# PS2Kbd.net
KiCad netlist of a schematic drawn in EAGLE
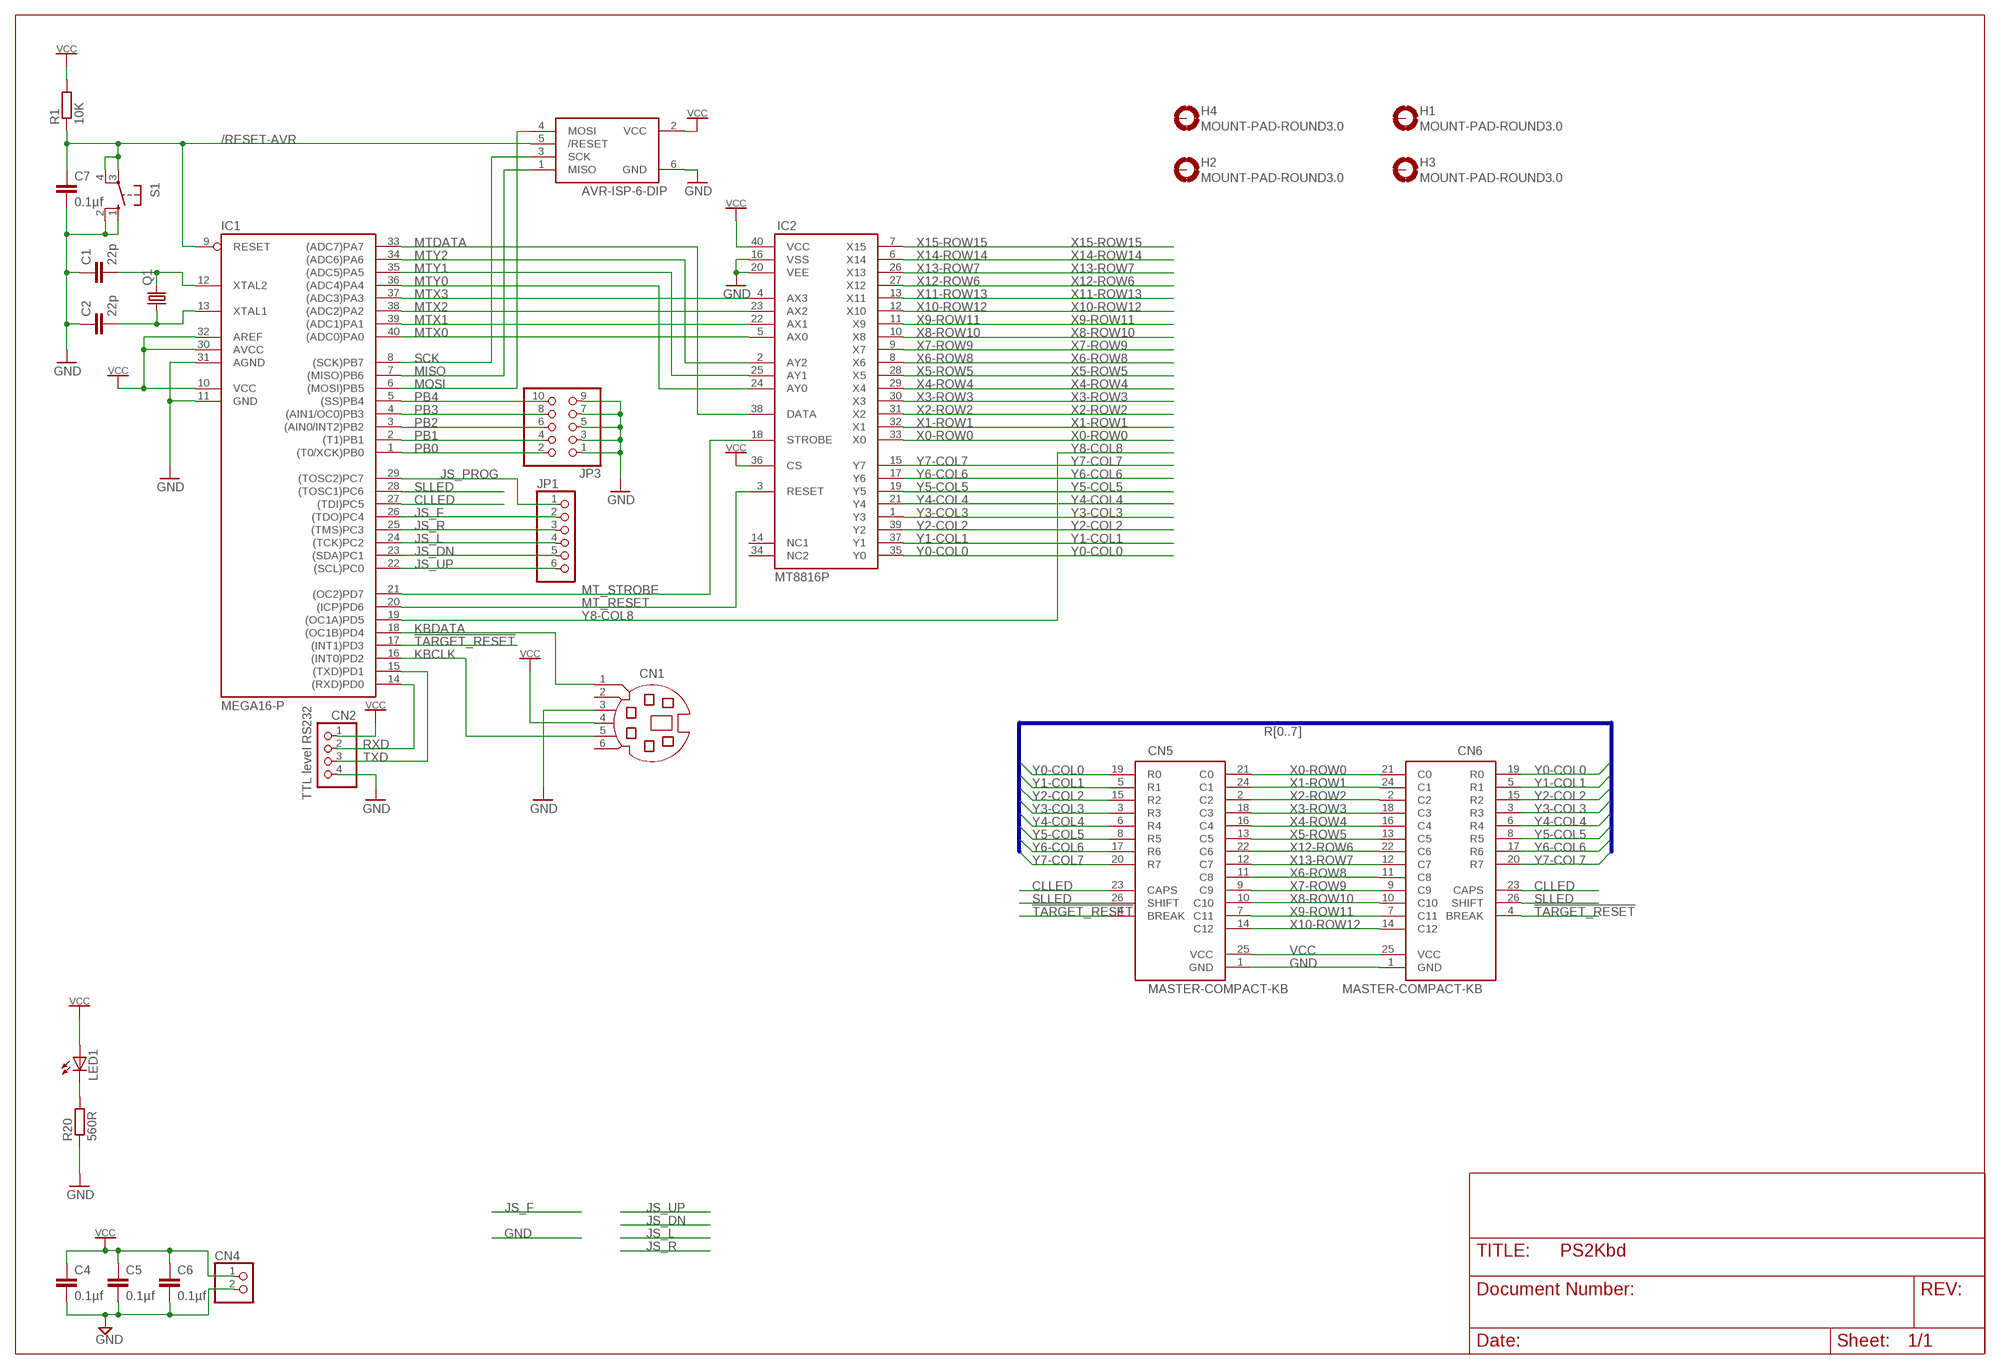
[diagram p0: schematic, sheet 1]

(export (version "E")
  (design (tool "Eeschema 10.0.6"))
  (components
    (comp (ref "C1")
      (value "22p")
      (footprint "eagle-import:C025-025X050")
      (libsource (lib "eagle-import") (part "C-EU025-025X050"))
    )
    (comp (ref "C2")
      (value "22p")
      (footprint "eagle-import:C025-025X050")
      (libsource (lib "eagle-import") (part "C-EU025-025X050"))
    )
    (comp (ref "C4")
      (value "0.1µf")
      (footprint "eagle-import:C025-025X050")
      (libsource (lib "eagle-import") (part "C-EU025-025X050"))
    )
    (comp (ref "C5")
      (value "0.1µf")
      (footprint "eagle-import:C025-025X050")
      (libsource (lib "eagle-import") (part "C-EU025-025X050"))
    )
    (comp (ref "C6")
      (value "0.1µf")
      (footprint "eagle-import:C025-025X050")
      (libsource (lib "eagle-import") (part "C-EU025-025X050"))
    )
    (comp (ref "C7")
      (value "0.1µf")
      (footprint "eagle-import:C025-025X050")
      (libsource (lib "eagle-import") (part "C-EU025-025X050"))
    )
    (comp (ref "CN1")
      (value "MD06SS")
      (footprint "eagle-import:MDIN06SS")
      (libsource (lib "eagle-import") (part "MD06SS"))
    )
    (comp (ref "CN2")
      (value "PINHD-1X4")
      (footprint "eagle-import:1X04")
      (libsource (lib "eagle-import") (part "PINHD-1X4"))
    )
    (comp (ref "CN3")
      (value "AVR-ISP-6-DIP")
      (footprint "eagle-import:2X3")
      (libsource (lib "eagle-import") (part "AVR-ISP-6-DIP"))
    )
    (comp (ref "CN4")
      (value "PINHD-1X2")
      (footprint "eagle-import:1X02")
      (libsource (lib "eagle-import") (part "PINHD-1X2"))
    )
    (comp (ref "CN5")
      (value "MASTER-COMPACT-KB")
      (footprint "eagle-import:2X13")
      (libsource (lib "eagle-import") (part "MASTER-COMPACT-KB"))
    )
    (comp (ref "CN6")
      (value "MASTER-COMPACT-KB")
      (footprint "eagle-import:2X13")
      (libsource (lib "eagle-import") (part "MASTER-COMPACT-KB"))
    )
    (comp (ref "H1")
      (value "MOUNT-PAD-ROUND3.0")
      (footprint "eagle-import:3,0-PAD")
      (libsource (lib "eagle-import") (part "MOUNT-PAD-ROUND3.0"))
    )
    (comp (ref "H2")
      (value "MOUNT-PAD-ROUND3.0")
      (footprint "eagle-import:3,0-PAD")
      (libsource (lib "eagle-import") (part "MOUNT-PAD-ROUND3.0"))
    )
    (comp (ref "H3")
      (value "MOUNT-PAD-ROUND3.0")
      (footprint "eagle-import:3,0-PAD")
      (libsource (lib "eagle-import") (part "MOUNT-PAD-ROUND3.0"))
    )
    (comp (ref "H4")
      (value "MOUNT-PAD-ROUND3.0")
      (footprint "eagle-import:3,0-PAD")
      (libsource (lib "eagle-import") (part "MOUNT-PAD-ROUND3.0"))
    )
    (comp (ref "IC1")
      (value "MEGA16-P")
      (footprint "eagle-import:DIL40")
      (libsource (lib "eagle-import") (part "MEGA16-P"))
    )
    (comp (ref "IC2")
      (value "MT8816P")
      (footprint "eagle-import:DIL40")
      (libsource (lib "eagle-import") (part "MT8816P"))
    )
    (comp (ref "JP1")
      (value "PINHD-1X6")
      (footprint "eagle-import:1X06")
      (libsource (lib "eagle-import") (part "PINHD-1X6"))
    )
    (comp (ref "JP3")
      (value "PINHD-2X5")
      (footprint "eagle-import:2X05")
      (libsource (lib "eagle-import") (part "PINHD-2X5"))
    )
    (comp (ref "LED1")
      (value "LED3MM")
      (footprint "eagle-import:LED3MM")
      (libsource (lib "eagle-import") (part "LED3MM"))
    )
    (comp (ref "Q1")
      (value "CRYSTALHC49S")
      (footprint "eagle-import:HC49_S")
      (libsource (lib "eagle-import") (part "CRYSTALHC49S"))
    )
    (comp (ref "R1")
      (value "10K")
      (footprint "eagle-import:0207_10")
      (libsource (lib "eagle-import") (part "R-EU_0207/10"))
    )
    (comp (ref "R20")
      (value "560R")
      (footprint "eagle-import:0207_10")
      (libsource (lib "eagle-import") (part "R-EU_0207/10"))
    )
    (comp (ref "S1")
      (value "10-XX")
      (footprint "eagle-import:B3F-10XX")
      (fields (field (name "MPN") "B3F-1000"))
      (libsource (lib "eagle-import") (part "10-XX"))
    )
  )
  (nets
    (net (code "9") (name "/CLLED") (class "Default")
      (node (ref "CN5") (pin "23") (pinfunction "CAPS_23") (pintype "bidirectional"))
      (node (ref "CN6") (pin "23") (pinfunction "CAPS_23") (pintype "bidirectional"))
      (node (ref "IC1") (pin "27") (pinfunction "(TDI)PC5_27") (pintype "bidirectional"))
    )
    (net (code "10") (name "/JS_DN") (class "Default")
      (node (ref "IC1") (pin "23") (pinfunction "(SDA)PC1_23") (pintype "bidirectional"))
      (node (ref "JP1") (pin "5") (pinfunction "5_5") (pintype "passive"))
    )
    (net (code "11") (name "/JS_F") (class "Default")
      (node (ref "IC1") (pin "26") (pinfunction "(TDO)PC4_26") (pintype "bidirectional"))
      (node (ref "JP1") (pin "2") (pinfunction "2_2") (pintype "passive"))
    )
    (net (code "12") (name "/JS_L") (class "Default")
      (node (ref "IC1") (pin "24") (pinfunction "(TCK)PC2_24") (pintype "bidirectional"))
      (node (ref "JP1") (pin "4") (pinfunction "4_4") (pintype "passive"))
    )
    (net (code "13") (name "/JS_PROG") (class "Default")
      (node (ref "IC1") (pin "29") (pinfunction "(TOSC2)PC7_29") (pintype "bidirectional"))
      (node (ref "JP1") (pin "1") (pinfunction "1_1") (pintype "passive"))
    )
    (net (code "14") (name "/JS_R") (class "Default")
      (node (ref "IC1") (pin "25") (pinfunction "(TMS)PC3_25") (pintype "bidirectional"))
      (node (ref "JP1") (pin "3") (pinfunction "3_3") (pintype "passive"))
    )
    (net (code "15") (name "/JS_UP") (class "Default")
      (node (ref "IC1") (pin "22") (pinfunction "(SCL)PC0_22") (pintype "bidirectional"))
      (node (ref "JP1") (pin "6") (pinfunction "6_6") (pintype "passive"))
    )
    (net (code "16") (name "/KBCLK") (class "Default")
      (node (ref "CN1") (pin "5") (pinfunction "5_5") (pintype "passive"))
      (node (ref "IC1") (pin "16") (pinfunction "(INT0)PD2_16") (pintype "bidirectional"))
    )
    (net (code "17") (name "/KBDATA") (class "Default")
      (node (ref "CN1") (pin "1") (pinfunction "1_1") (pintype "passive"))
      (node (ref "IC1") (pin "18") (pinfunction "(OC1B)PD4_18") (pintype "bidirectional"))
    )
    (net (code "18") (name "/MISO") (class "Default")
      (node (ref "CN3") (pin "1") (pinfunction "MISO_1") (pintype "bidirectional"))
      (node (ref "IC1") (pin "7") (pinfunction "(MISO)PB6_7") (pintype "bidirectional"))
    )
    (net (code "19") (name "/MOSI") (class "Default")
      (node (ref "CN3") (pin "4") (pinfunction "MOSI_4") (pintype "bidirectional"))
      (node (ref "IC1") (pin "6") (pinfunction "(MOSI)PB5_6") (pintype "bidirectional"))
    )
    (net (code "20") (name "/MTDATA") (class "Default")
      (node (ref "IC1") (pin "33") (pinfunction "(ADC7)PA7_33") (pintype "bidirectional"))
      (node (ref "IC2") (pin "38") (pinfunction "DATA_38") (pintype "input"))
    )
    (net (code "21") (name "/MTX0") (class "Default")
      (node (ref "IC1") (pin "40") (pinfunction "(ADC0)PA0_40") (pintype "bidirectional"))
      (node (ref "IC2") (pin "5") (pinfunction "AX0_5") (pintype "input"))
    )
    (net (code "22") (name "/MTX1") (class "Default")
      (node (ref "IC1") (pin "39") (pinfunction "(ADC1)PA1_39") (pintype "bidirectional"))
      (node (ref "IC2") (pin "22") (pinfunction "AX1_22") (pintype "input"))
    )
    (net (code "23") (name "/MTX2") (class "Default")
      (node (ref "IC1") (pin "38") (pinfunction "(ADC2)PA2_38") (pintype "bidirectional"))
      (node (ref "IC2") (pin "23") (pinfunction "AX2_23") (pintype "input"))
    )
    (net (code "24") (name "/MTX3") (class "Default")
      (node (ref "IC1") (pin "37") (pinfunction "(ADC3)PA3_37") (pintype "bidirectional"))
      (node (ref "IC2") (pin "4") (pinfunction "AX3_4") (pintype "input"))
    )
    (net (code "25") (name "/MTY0") (class "Default")
      (node (ref "IC1") (pin "36") (pinfunction "(ADC4)PA4_36") (pintype "bidirectional"))
      (node (ref "IC2") (pin "24") (pinfunction "AY0_24") (pintype "input"))
    )
    (net (code "26") (name "/MTY1") (class "Default")
      (node (ref "IC1") (pin "35") (pinfunction "(ADC5)PA5_35") (pintype "bidirectional"))
      (node (ref "IC2") (pin "25") (pinfunction "AY1_25") (pintype "input"))
    )
    (net (code "27") (name "/MTY2") (class "Default")
      (node (ref "IC1") (pin "34") (pinfunction "(ADC6)PA6_34") (pintype "bidirectional"))
      (node (ref "IC2") (pin "2") (pinfunction "AY2_2") (pintype "input"))
    )
    (net (code "28") (name "/MT_RESET") (class "Default")
      (node (ref "IC1") (pin "20") (pinfunction "(ICP)PD6_20") (pintype "bidirectional"))
      (node (ref "IC2") (pin "3") (pinfunction "RESET_3") (pintype "input"))
    )
    (net (code "29") (name "/MT_STROBE") (class "Default")
      (node (ref "IC1") (pin "21") (pinfunction "(OC2)PD7_21") (pintype "bidirectional"))
      (node (ref "IC2") (pin "18") (pinfunction "STROBE_18") (pintype "input"))
    )
    (net (code "30") (name "/PB0") (class "Default")
      (node (ref "IC1") (pin "1") (pinfunction "(T0/XCK)PB0_1") (pintype "bidirectional"))
      (node (ref "JP3") (pin "2") (pinfunction "2_2") (pintype "passive"))
    )
    (net (code "31") (name "/PB1") (class "Default")
      (node (ref "IC1") (pin "2") (pinfunction "(T1)PB1_2") (pintype "bidirectional"))
      (node (ref "JP3") (pin "4") (pinfunction "4_4") (pintype "passive"))
    )
    (net (code "32") (name "/PB2") (class "Default")
      (node (ref "IC1") (pin "3") (pinfunction "(AIN0/INT2)PB2_3") (pintype "bidirectional"))
      (node (ref "JP3") (pin "6") (pinfunction "6_6") (pintype "passive"))
    )
    (net (code "33") (name "/PB3") (class "Default")
      (node (ref "IC1") (pin "4") (pinfunction "(AIN1/OC0)PB3_4") (pintype "bidirectional"))
      (node (ref "JP3") (pin "8") (pinfunction "8_8") (pintype "passive"))
    )
    (net (code "34") (name "/PB4") (class "Default")
      (node (ref "IC1") (pin "5") (pinfunction "(SS)PB4_5") (pintype "bidirectional"))
      (node (ref "JP3") (pin "10") (pinfunction "10_10") (pintype "passive"))
    )
    (net (code "35") (name "/RXD") (class "Default")
      (node (ref "CN2") (pin "2") (pinfunction "2_2") (pintype "passive"))
      (node (ref "IC1") (pin "14") (pinfunction "(RXD)PD0_14") (pintype "bidirectional"))
    )
    (net (code "37") (name "/SCK") (class "Default")
      (node (ref "CN3") (pin "3") (pinfunction "SCK_3") (pintype "bidirectional"))
      (node (ref "IC1") (pin "8") (pinfunction "(SCK)PB7_8") (pintype "bidirectional"))
    )
    (net (code "38") (name "/SLLED") (class "Default")
      (node (ref "CN5") (pin "26") (pinfunction "SHIFT_26") (pintype "bidirectional"))
      (node (ref "CN6") (pin "26") (pinfunction "SHIFT_26") (pintype "bidirectional"))
      (node (ref "IC1") (pin "28") (pinfunction "(TOSC1)PC6_28") (pintype "bidirectional"))
    )
    (net (code "39") (name "/TXD") (class "Default")
      (node (ref "CN2") (pin "3") (pinfunction "3_3") (pintype "passive"))
      (node (ref "IC1") (pin "15") (pinfunction "(TXD)PD1_15") (pintype "bidirectional"))
    )
    (net (code "40") (name "/X0-ROW0") (class "Default")
      (node (ref "CN5") (pin "21") (pinfunction "C0_21") (pintype "bidirectional"))
      (node (ref "CN6") (pin "21") (pinfunction "C0_21") (pintype "bidirectional"))
      (node (ref "IC2") (pin "33") (pinfunction "X0_33") (pintype "bidirectional"))
    )
    (net (code "41") (name "/X1-ROW1") (class "Default")
      (node (ref "CN5") (pin "24") (pinfunction "C1_24") (pintype "bidirectional"))
      (node (ref "CN6") (pin "24") (pinfunction "C1_24") (pintype "bidirectional"))
      (node (ref "IC2") (pin "32") (pinfunction "X1_32") (pintype "bidirectional"))
    )
    (net (code "42") (name "/X2-ROW2") (class "Default")
      (node (ref "CN5") (pin "2") (pinfunction "C2_2") (pintype "bidirectional"))
      (node (ref "CN6") (pin "2") (pinfunction "C2_2") (pintype "bidirectional"))
      (node (ref "IC2") (pin "31") (pinfunction "X2_31") (pintype "bidirectional"))
    )
    (net (code "43") (name "/X3-ROW3") (class "Default")
      (node (ref "CN5") (pin "18") (pinfunction "C3_18") (pintype "bidirectional"))
      (node (ref "CN6") (pin "18") (pinfunction "C3_18") (pintype "bidirectional"))
      (node (ref "IC2") (pin "30") (pinfunction "X3_30") (pintype "bidirectional"))
    )
    (net (code "44") (name "/X4-ROW4") (class "Default")
      (node (ref "CN5") (pin "16") (pinfunction "C4_16") (pintype "bidirectional"))
      (node (ref "CN6") (pin "16") (pinfunction "C4_16") (pintype "bidirectional"))
      (node (ref "IC2") (pin "29") (pinfunction "X4_29") (pintype "bidirectional"))
    )
    (net (code "45") (name "/X5-ROW5") (class "Default")
      (node (ref "CN5") (pin "13") (pinfunction "C5_13") (pintype "bidirectional"))
      (node (ref "CN6") (pin "13") (pinfunction "C5_13") (pintype "bidirectional"))
      (node (ref "IC2") (pin "28") (pinfunction "X5_28") (pintype "bidirectional"))
    )
    (net (code "46") (name "/X6-ROW8") (class "Default")
      (node (ref "CN5") (pin "11") (pinfunction "C8_11") (pintype "bidirectional"))
      (node (ref "CN6") (pin "11") (pinfunction "C8_11") (pintype "bidirectional"))
      (node (ref "IC2") (pin "8") (pinfunction "X6_8") (pintype "bidirectional"))
    )
    (net (code "47") (name "/X7-ROW9") (class "Default")
      (node (ref "CN5") (pin "9") (pinfunction "C9_9") (pintype "bidirectional"))
      (node (ref "CN6") (pin "9") (pinfunction "C9_9") (pintype "bidirectional"))
      (node (ref "IC2") (pin "9") (pinfunction "X7_9") (pintype "bidirectional"))
    )
    (net (code "48") (name "/X8-ROW10") (class "Default")
      (node (ref "CN5") (pin "10") (pinfunction "C10_10") (pintype "bidirectional"))
      (node (ref "CN6") (pin "10") (pinfunction "C10_10") (pintype "bidirectional"))
      (node (ref "IC2") (pin "10") (pinfunction "X8_10") (pintype "bidirectional"))
    )
    (net (code "49") (name "/X9-ROW11") (class "Default")
      (node (ref "CN5") (pin "7") (pinfunction "C11_7") (pintype "bidirectional"))
      (node (ref "CN6") (pin "7") (pinfunction "C11_7") (pintype "bidirectional"))
      (node (ref "IC2") (pin "11") (pinfunction "X9_11") (pintype "bidirectional"))
    )
    (net (code "50") (name "/X10-ROW12") (class "Default")
      (node (ref "CN5") (pin "14") (pinfunction "C12_14") (pintype "bidirectional"))
      (node (ref "CN6") (pin "14") (pinfunction "C12_14") (pintype "bidirectional"))
      (node (ref "IC2") (pin "12") (pinfunction "X10_12") (pintype "bidirectional"))
    )
    (net (code "51") (name "/X11-ROW13") (class "Default")
      (node (ref "IC2") (pin "13") (pinfunction "X11_13") (pintype "bidirectional"))
    )
    (net (code "52") (name "/X12-ROW6") (class "Default")
      (node (ref "CN5") (pin "22") (pinfunction "C6_22") (pintype "bidirectional"))
      (node (ref "CN6") (pin "22") (pinfunction "C6_22") (pintype "bidirectional"))
      (node (ref "IC2") (pin "27") (pinfunction "X12_27") (pintype "bidirectional"))
    )
    (net (code "53") (name "/X13-ROW7") (class "Default")
      (node (ref "CN5") (pin "12") (pinfunction "C7_12") (pintype "bidirectional"))
      (node (ref "CN6") (pin "12") (pinfunction "C7_12") (pintype "bidirectional"))
      (node (ref "IC2") (pin "26") (pinfunction "X13_26") (pintype "bidirectional"))
    )
    (net (code "54") (name "/X14-ROW14") (class "Default")
      (node (ref "IC2") (pin "6") (pinfunction "X14_6") (pintype "bidirectional"))
    )
    (net (code "55") (name "/X15-ROW15") (class "Default")
      (node (ref "IC2") (pin "7") (pinfunction "X15_7") (pintype "bidirectional"))
    )
    (net (code "56") (name "/Y0-COL0") (class "Default")
      (node (ref "CN5") (pin "19") (pinfunction "R0_19") (pintype "bidirectional"))
      (node (ref "CN6") (pin "19") (pinfunction "R0_19") (pintype "bidirectional"))
      (node (ref "IC2") (pin "35") (pinfunction "Y0_35") (pintype "bidirectional"))
    )
    (net (code "57") (name "/Y1-COL1") (class "Default")
      (node (ref "CN5") (pin "5") (pinfunction "R1_5") (pintype "bidirectional"))
      (node (ref "CN6") (pin "5") (pinfunction "R1_5") (pintype "bidirectional"))
      (node (ref "IC2") (pin "37") (pinfunction "Y1_37") (pintype "bidirectional"))
    )
    (net (code "58") (name "/Y2-COL2") (class "Default")
      (node (ref "CN5") (pin "15") (pinfunction "R2_15") (pintype "bidirectional"))
      (node (ref "CN6") (pin "15") (pinfunction "R2_15") (pintype "bidirectional"))
      (node (ref "IC2") (pin "39") (pinfunction "Y2_39") (pintype "bidirectional"))
    )
    (net (code "59") (name "/Y3-COL3") (class "Default")
      (node (ref "CN5") (pin "3") (pinfunction "R3_3") (pintype "bidirectional"))
      (node (ref "CN6") (pin "3") (pinfunction "R3_3") (pintype "bidirectional"))
      (node (ref "IC2") (pin "1") (pinfunction "Y3_1") (pintype "bidirectional"))
    )
    (net (code "60") (name "/Y4-COL4") (class "Default")
      (node (ref "CN5") (pin "6") (pinfunction "R4_6") (pintype "bidirectional"))
      (node (ref "CN6") (pin "6") (pinfunction "R4_6") (pintype "bidirectional"))
      (node (ref "IC2") (pin "21") (pinfunction "Y4_21") (pintype "bidirectional"))
    )
    (net (code "61") (name "/Y5-COL5") (class "Default")
      (node (ref "CN5") (pin "8") (pinfunction "R5_8") (pintype "bidirectional"))
      (node (ref "CN6") (pin "8") (pinfunction "R5_8") (pintype "bidirectional"))
      (node (ref "IC2") (pin "19") (pinfunction "Y5_19") (pintype "bidirectional"))
    )
    (net (code "62") (name "/Y6-COL6") (class "Default")
      (node (ref "CN5") (pin "17") (pinfunction "R6_17") (pintype "bidirectional"))
      (node (ref "CN6") (pin "17") (pinfunction "R6_17") (pintype "bidirectional"))
      (node (ref "IC2") (pin "17") (pinfunction "Y6_17") (pintype "bidirectional"))
    )
    (net (code "63") (name "/Y7-COL7") (class "Default")
      (node (ref "CN5") (pin "20") (pinfunction "R7_20") (pintype "bidirectional"))
      (node (ref "CN6") (pin "20") (pinfunction "R7_20") (pintype "bidirectional"))
      (node (ref "IC2") (pin "15") (pinfunction "Y7_15") (pintype "bidirectional"))
    )
    (net (code "64") (name "/Y8-COL8") (class "Default")
      (node (ref "IC1") (pin "19") (pinfunction "(OC1A)PD5_19") (pintype "bidirectional"))
    )
    (net (code "65") (name "/{slash}RESET-AVR") (class "Default")
      (node (ref "C7") (pin "1") (pinfunction "1_1") (pintype "passive"))
      (node (ref "CN3") (pin "5") (pinfunction "/RESET_5") (pintype "bidirectional"))
      (node (ref "IC1") (pin "9") (pinfunction "RESET_9") (pintype "input"))
      (node (ref "R1") (pin "1") (pinfunction "1_1") (pintype "passive"))
      (node (ref "S1") (pin "3") (pinfunction "P_3") (pintype "passive"))
      (node (ref "S1") (pin "4") (pinfunction "P1_4") (pintype "passive"))
    )
    (net (code "66") (name "/~{TARGET_RESET}") (class "Default")
      (node (ref "CN5") (pin "4") (pinfunction "BREAK_4") (pintype "bidirectional"))
      (node (ref "CN6") (pin "4") (pinfunction "BREAK_4") (pintype "bidirectional"))
      (node (ref "IC1") (pin "17") (pinfunction "(INT1)PD3_17") (pintype "bidirectional"))
    )
    (net (code "67") (name "GND") (class "Default")
      (node (ref "C1") (pin "1") (pinfunction "1_1") (pintype "passive"))
      (node (ref "C2") (pin "1") (pinfunction "1_1") (pintype "passive"))
      (node (ref "C4") (pin "2") (pinfunction "2_2") (pintype "passive"))
      (node (ref "C5") (pin "2") (pinfunction "2_2") (pintype "passive"))
      (node (ref "C6") (pin "2") (pinfunction "2_2") (pintype "passive"))
      (node (ref "C7") (pin "2") (pinfunction "2_2") (pintype "passive"))
      (node (ref "CN1") (pin "3") (pinfunction "3_3") (pintype "passive"))
      (node (ref "CN2") (pin "4") (pinfunction "4_4") (pintype "passive"))
      (node (ref "CN3") (pin "6") (pinfunction "GND_6") (pintype "power_in"))
      (node (ref "CN4") (pin "2") (pinfunction "2_2") (pintype "passive"))
      (node (ref "CN5") (pin "1") (pinfunction "GND_1") (pintype "bidirectional"))
      (node (ref "CN6") (pin "1") (pinfunction "GND_1") (pintype "bidirectional"))
      (node (ref "IC1") (pin "11") (pinfunction "GND_11") (pintype "power_in"))
      (node (ref "IC1") (pin "31") (pinfunction "AGND_31") (pintype "power_in"))
      (node (ref "IC2") (pin "16") (pinfunction "VSS_16") (pintype "power_in"))
      (node (ref "IC2") (pin "20") (pinfunction "VEE_20") (pintype "power_in"))
      (node (ref "JP3") (pin "1") (pinfunction "1_1") (pintype "passive"))
      (node (ref "JP3") (pin "3") (pinfunction "3_3") (pintype "passive"))
      (node (ref "JP3") (pin "5") (pinfunction "5_5") (pintype "passive"))
      (node (ref "JP3") (pin "7") (pinfunction "7_7") (pintype "passive"))
      (node (ref "JP3") (pin "9") (pinfunction "9_9") (pintype "passive"))
      (node (ref "R20") (pin "1") (pinfunction "1_1") (pintype "passive"))
      (node (ref "S1") (pin "1") (pinfunction "S_1") (pintype "passive"))
      (node (ref "S1") (pin "2") (pinfunction "S1_2") (pintype "passive"))
    )
    (net (code "68") (name "Net-(IC1-XTAL1)") (class "Default")
      (node (ref "C2") (pin "2") (pinfunction "2_2") (pintype "passive"))
      (node (ref "IC1") (pin "13") (pinfunction "XTAL1_13") (pintype "bidirectional"))
      (node (ref "Q1") (pin "1") (pinfunction "1_1") (pintype "passive"))
    )
    (net (code "69") (name "Net-(IC1-XTAL2)") (class "Default")
      (node (ref "C1") (pin "2") (pinfunction "2_2") (pintype "passive"))
      (node (ref "IC1") (pin "12") (pinfunction "XTAL2_12") (pintype "bidirectional"))
      (node (ref "Q1") (pin "2") (pinfunction "2_2") (pintype "passive"))
    )
    (net (code "70") (name "Net-(LED1-C)") (class "Default")
      (node (ref "LED1") (pin "K") (pinfunction "C_K") (pintype "passive"))
      (node (ref "R20") (pin "2") (pinfunction "2_2") (pintype "passive"))
    )
    (net (code "71") (name "VCC") (class "Default")
      (node (ref "C4") (pin "1") (pinfunction "1_1") (pintype "passive"))
      (node (ref "C5") (pin "1") (pinfunction "1_1") (pintype "passive"))
      (node (ref "C6") (pin "1") (pinfunction "1_1") (pintype "passive"))
      (node (ref "CN1") (pin "4") (pinfunction "4_4") (pintype "passive"))
      (node (ref "CN2") (pin "1") (pinfunction "1_1") (pintype "passive"))
      (node (ref "CN3") (pin "2") (pinfunction "VCC_2") (pintype "power_in"))
      (node (ref "CN4") (pin "1") (pinfunction "1_1") (pintype "passive"))
      (node (ref "CN5") (pin "25") (pinfunction "VCC_25") (pintype "bidirectional"))
      (node (ref "CN6") (pin "25") (pinfunction "VCC_25") (pintype "bidirectional"))
      (node (ref "IC1") (pin "10") (pinfunction "VCC_10") (pintype "power_in"))
      (node (ref "IC1") (pin "30") (pinfunction "AVCC_30") (pintype "power_in"))
      (node (ref "IC1") (pin "32") (pinfunction "AREF_32") (pintype "power_in"))
      (node (ref "IC2") (pin "36") (pinfunction "CS_36") (pintype "input"))
      (node (ref "IC2") (pin "40") (pinfunction "VCC_40") (pintype "power_in"))
      (node (ref "LED1") (pin "A") (pinfunction "A_A") (pintype "passive"))
      (node (ref "R1") (pin "2") (pinfunction "2_2") (pintype "passive"))
    )
    (net (code "72") (name "unconnected-(CN1-Pad2)") (class "Default")
      (node (ref "CN1") (pin "2") (pinfunction "2_2") (pintype "passive"))
    )
    (net (code "73") (name "unconnected-(CN1-Pad6)") (class "Default")
      (node (ref "CN1") (pin "6") (pinfunction "6_6") (pintype "passive"))
    )
    (net (code "74") (name "unconnected-(H1-MOUNT-PadB3,0)") (class "Default")
      (node (ref "H1") (pin "B3,0") (pinfunction "MOUNT_B3,0") (pintype "passive"))
    )
    (net (code "75") (name "unconnected-(H2-MOUNT-PadB3,0)") (class "Default")
      (node (ref "H2") (pin "B3,0") (pinfunction "MOUNT_B3,0") (pintype "passive"))
    )
    (net (code "76") (name "unconnected-(H3-MOUNT-PadB3,0)") (class "Default")
      (node (ref "H3") (pin "B3,0") (pinfunction "MOUNT_B3,0") (pintype "passive"))
    )
    (net (code "77") (name "unconnected-(H4-MOUNT-PadB3,0)") (class "Default")
      (node (ref "H4") (pin "B3,0") (pinfunction "MOUNT_B3,0") (pintype "passive"))
    )
    (net (code "78") (name "unconnected-(IC2-NC1-Pad14)") (class "Default")
      (node (ref "IC2") (pin "14") (pinfunction "NC1_14") (pintype "no_connect"))
    )
    (net (code "79") (name "unconnected-(IC2-NC2-Pad34)") (class "Default")
      (node (ref "IC2") (pin "34") (pinfunction "NC2_34") (pintype "no_connect"))
    )
  )
)
